# Sheet1.net
KiCad netlist of a schematic drawn in Altium Designer
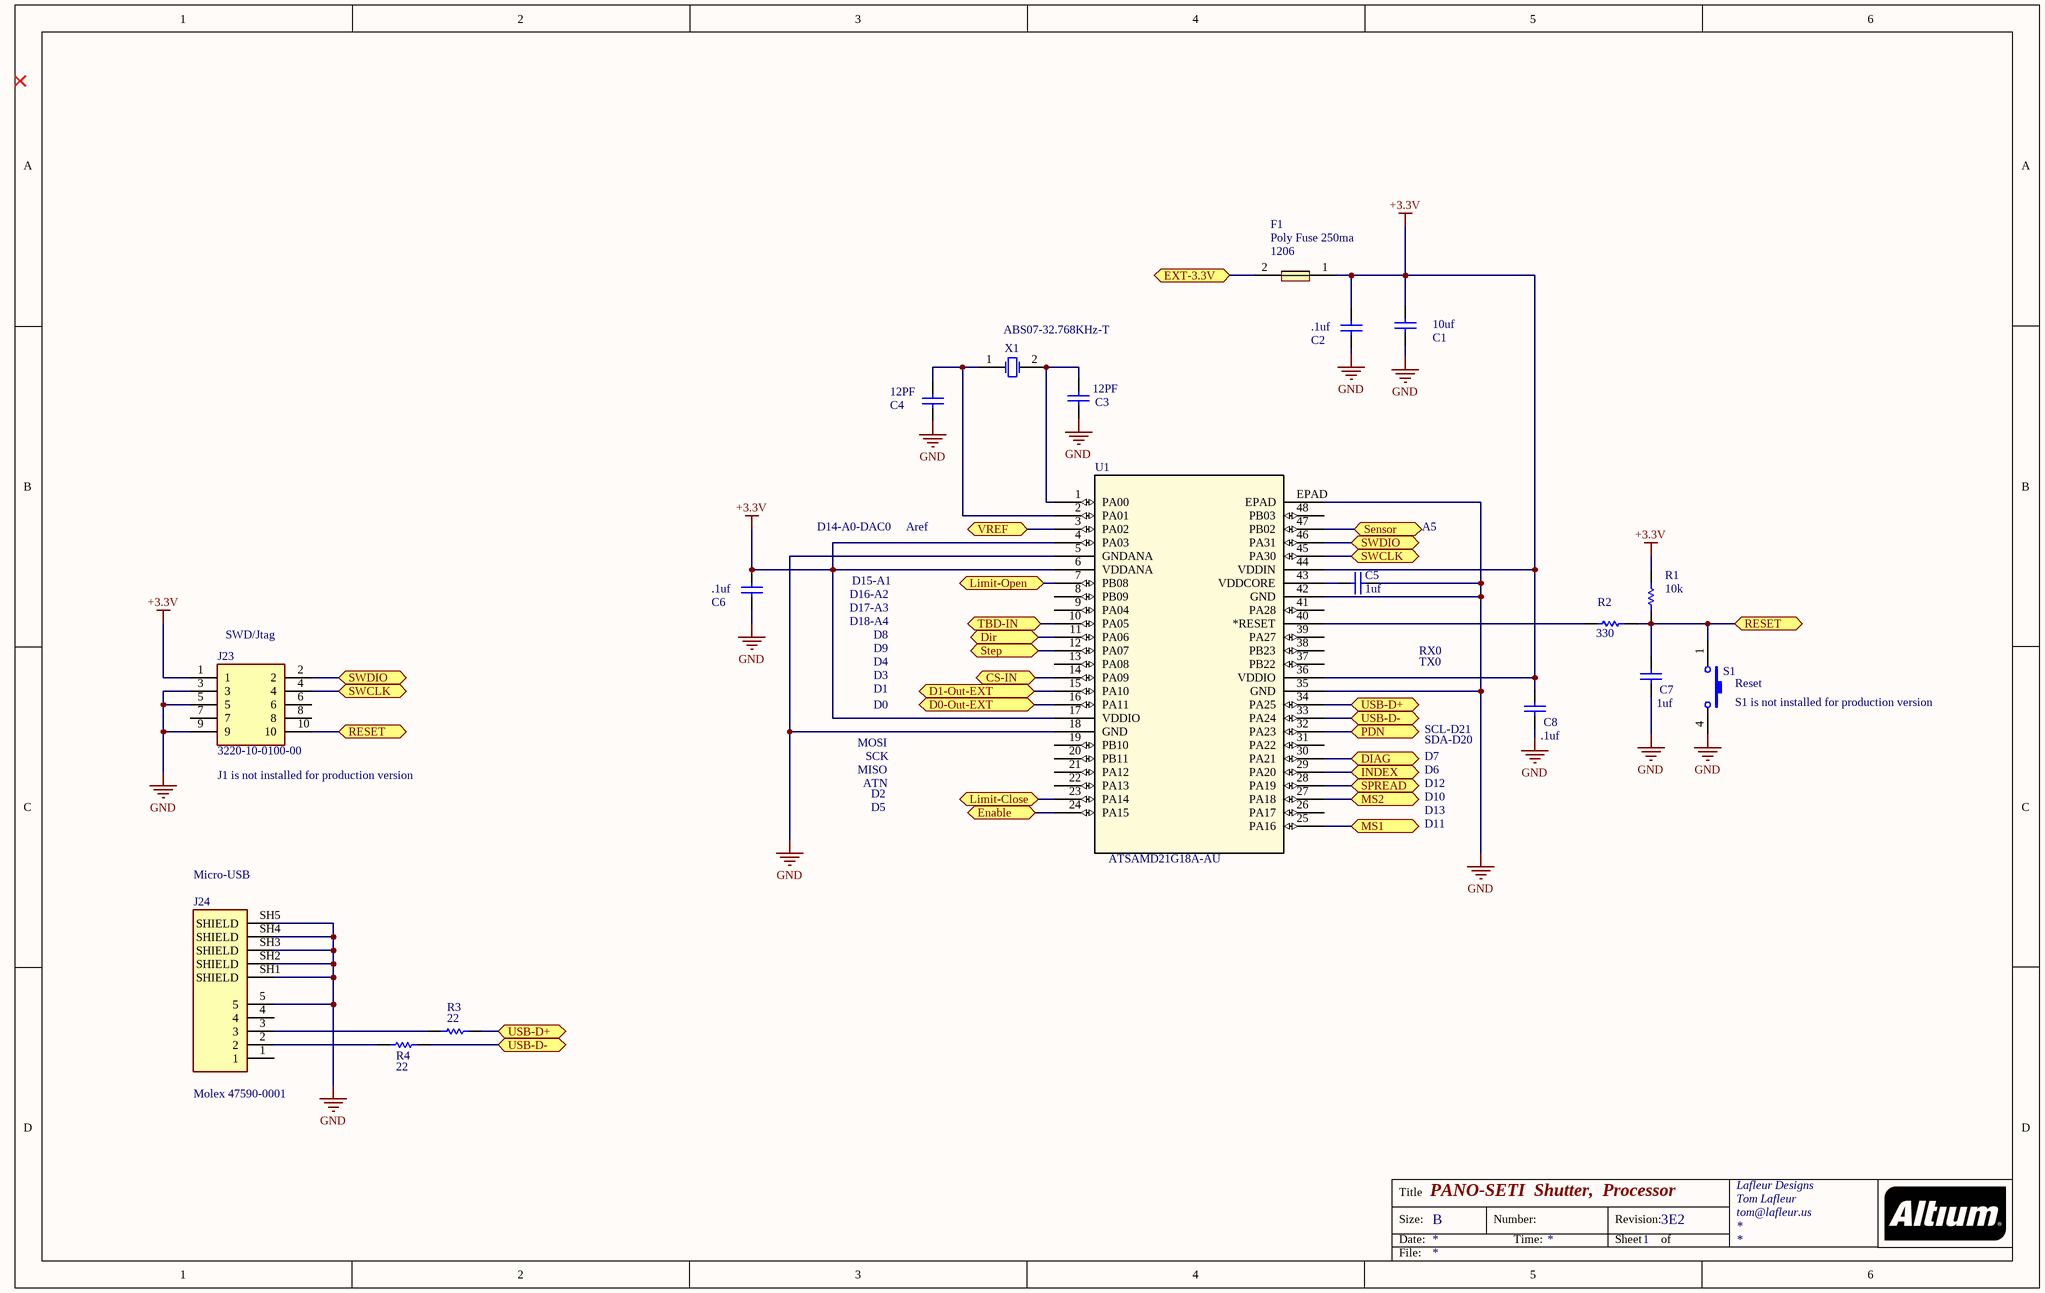
[diagram p0: Sheet1.SchDoc]

(export (version "E")
  (design (tool "Eeschema 10.0.6"))
  (components
    (comp (ref "C1")
      (value "10uf")
      (footprint "6-0805")
      (description "Capacitor")
      (libsource (lib "Winmor-Demo-R2") (part "CAP_2"))
    )
    (comp (ref "C2")
      (value ".1uf")
      (footprint "6-0805")
      (description "Capacitor")
      (libsource (lib "Winmor-Demo-R2") (part "CAP_2"))
    )
    (comp (ref "C3")
      (value "12PF")
      (footprint "6-0805")
      (description "Capacitor")
      (libsource (lib "Winmor-Demo-R2") (part "CAP_2"))
    )
    (comp (ref "C4")
      (value "12PF")
      (footprint "6-0805")
      (description "Capacitor")
      (libsource (lib "Winmor-Demo-R2") (part "CAP_2"))
    )
    (comp (ref "C5")
      (value "1uf")
      (footprint "6-0805")
      (description "Capacitor")
      (libsource (lib "Winmor-Demo-R2") (part "CAP_2"))
    )
    (comp (ref "C6")
      (value ".1uf")
      (footprint "6-0805")
      (description "Capacitor")
      (libsource (lib "Winmor-Demo-R2") (part "CAP_2"))
    )
    (comp (ref "C7")
      (value "1uf")
      (footprint "6-0805")
      (description "Capacitor")
      (libsource (lib "Winmor-Demo-R2") (part "CAP_2"))
    )
    (comp (ref "C8")
      (value ".1uf")
      (footprint "6-0805")
      (description "Capacitor")
      (libsource (lib "Winmor-Demo-R2") (part "CAP_2"))
    )
    (comp (ref "F1")
      (value "Poly Fuse 250ma")
      (footprint "8-1206")
      (description "Poly Fuse")
      (libsource (lib "N2K Project") (part "Poly Fuse"))
    )
    (comp (ref "J23")
      (value "3220-10-0100-00")
      (footprint "SHDR10W41P127_2X5_1265X510X565P")
      (description "Connector")
      (libsource (lib "*") (part "3220-10-0100-00"))
    )
    (comp (ref "J24")
      (value "Molex 47590-0001")
      (footprint "Molex 47590-0001")
      (description "USB - micro AB Receptacle Connector 5 Position Surface Mount, Right Angle; Through Hole")
      (fields (field (name "MF") "Molex") (field (name "MP") "47590-0001"))
      (libsource (lib "SnapEDAsch") (part "47590-0001"))
    )
    (comp (ref "R1")
      (value "10k")
      (footprint "6-0805")
      (description "Precision Thick Film Chip Resistor, 10 Ohm to 2.2M Ohm Range, 1% Tolerance, 1206 Size, 0.125 W")
      (fields (field (name "PUBLISHER") "Altium Limited"))
      (libsource (lib "N2K Project") (part "ERJ8EN"))
    )
    (comp (ref "R2")
      (value "330")
      (footprint "6-0805")
      (description "Precision Thick Film Chip Resistor, 10 Ohm to 2.2M Ohm Range, 1% Tolerance, 1206 Size, 0.125 W")
      (fields (field (name "PUBLISHER") "Altium Limited"))
      (libsource (lib "N2K Project") (part "ERJ8EN"))
    )
    (comp (ref "R3")
      (value "22")
      (footprint "6-0805")
      (description "Precision Thick Film Chip Resistor, 10 Ohm to 2.2M Ohm Range, 1% Tolerance, 1206 Size, 0.125 W")
      (fields (field (name "PUBLISHER") "Altium Limited"))
      (libsource (lib "N2K Project") (part "ERJ8EN"))
    )
    (comp (ref "R4")
      (value "22")
      (footprint "6-0805")
      (description "Precision Thick Film Chip Resistor, 10 Ohm to 2.2M Ohm Range, 1% Tolerance, 1206 Size, 0.125 W")
      (fields (field (name "PUBLISHER") "Altium Limited"))
      (libsource (lib "N2K Project") (part "ERJ8EN"))
    )
    (comp (ref "S1")
      (value "Reset")
      (footprint "SamacSys:KMR_2")
      (description "Switch")
      (fields (field (name "PUBLISHER") "Altium Limited"))
      (libsource (lib "Miscellaneous Devices") (part "SW-PB"))
    )
    (comp (ref "U1")
      (value "ATSAMD21G18A-AU")
      (footprint "TQFP48_7x7MC")
      (description "No Description Available")
      (fields (field (name "COPYRIGHT") "Copyright (C) 2018 Accelerated Designs. All rights reserved"))
      (libsource (lib "ATSAMD21G18") (part "ATSAMD21G18A-AU"))
    )
    (comp (ref "X1")
      (value "ABS07-32.768KHz-T")
      (footprint "ABRA-ABS07-2_V")
      (description "Crystal, 32.768 kHz, 12.5 pF, -40 to 85 degC, SMD Low Profile 3.2 x 1.5 x 0.9 mm, Tape and Reel")
      (fields (field (name "MANUFACTURER") "Abracon"))
      (libsource (lib "Altium Content Vault") (part "ABRA-ABS07-2"))
    )
  )
  (nets
    (net (code "1") (name "+3.3V") (class "Default")
      (node (ref "C1") (pin "1") (pinfunction "1_1") (pintype "passive"))
      (node (ref "C2") (pin "1") (pinfunction "1_1") (pintype "passive"))
      (node (ref "C6") (pin "1") (pinfunction "1_1") (pintype "passive"))
      (node (ref "C8") (pin "1") (pinfunction "1_1") (pintype "passive"))
      (node (ref "F1") (pin "1") (pinfunction "1_1") (pintype "passive"))
      (node (ref "J23") (pin "1") (pinfunction "1_1") (pintype "passive"))
      (node (ref "R1") (pin "1") (pinfunction "1_1") (pintype "passive"))
      (node (ref "U1") (pin "17") (pinfunction "VDDIO_17") (pintype "power_in"))
      (node (ref "U1") (pin "36") (pinfunction "VDDIO_36") (pintype "power_in"))
      (node (ref "U1") (pin "4") (pinfunction "PA03_4") (pintype "bidirectional"))
      (node (ref "U1") (pin "44") (pinfunction "VDDIN_44") (pintype "power_in"))
      (node (ref "U1") (pin "6") (pinfunction "VDDANA_6") (pintype "power_in"))
    )
    (net (code "2") (name "/CS-IN") (class "Default")
      (node (ref "U1") (pin "14") (pinfunction "PA09_14") (pintype "bidirectional"))
    )
    (net (code "3") (name "/D0-Out-EXT") (class "Default")
      (node (ref "U1") (pin "16") (pinfunction "PA11_16") (pintype "bidirectional"))
    )
    (net (code "4") (name "/D1-Out-EXT") (class "Default")
      (node (ref "U1") (pin "15") (pinfunction "PA10_15") (pintype "bidirectional"))
    )
    (net (code "5") (name "/DIAG") (class "Default")
      (node (ref "U1") (pin "30") (pinfunction "PA21_30") (pintype "bidirectional"))
    )
    (net (code "6") (name "/Dir") (class "Default")
      (node (ref "U1") (pin "11") (pinfunction "PA06_11") (pintype "bidirectional"))
    )
    (net (code "7") (name "/EXT-3.3V") (class "Default")
      (node (ref "F1") (pin "2") (pinfunction "2_2") (pintype "passive"))
    )
    (net (code "8") (name "/Enable") (class "Default")
      (node (ref "U1") (pin "24") (pinfunction "PA15_24") (pintype "bidirectional"))
    )
    (net (code "9") (name "/INDEX") (class "Default")
      (node (ref "U1") (pin "29") (pinfunction "PA20_29") (pintype "bidirectional"))
    )
    (net (code "10") (name "/Limit-Close") (class "Default")
      (node (ref "U1") (pin "23") (pinfunction "PA14_23") (pintype "bidirectional"))
    )
    (net (code "11") (name "/Limit-Open") (class "Default")
      (node (ref "U1") (pin "7") (pinfunction "PB08_7") (pintype "bidirectional"))
    )
    (net (code "12") (name "/MS1") (class "Default")
      (node (ref "U1") (pin "25") (pinfunction "PA16_25") (pintype "bidirectional"))
    )
    (net (code "13") (name "/MS2") (class "Default")
      (node (ref "U1") (pin "27") (pinfunction "PA18_27") (pintype "bidirectional"))
    )
    (net (code "14") (name "/PDN") (class "Default")
      (node (ref "U1") (pin "32") (pinfunction "PA23_32") (pintype "bidirectional"))
    )
    (net (code "15") (name "/RESET") (class "Default")
      (node (ref "C7") (pin "1") (pinfunction "1_1") (pintype "passive"))
      (node (ref "J23") (pin "10") (pinfunction "10_10") (pintype "passive"))
      (node (ref "R1") (pin "2") (pinfunction "2_2") (pintype "passive"))
      (node (ref "R2") (pin "2") (pinfunction "2_2") (pintype "passive"))
      (node (ref "S1") (pin "1") (pinfunction "1_1") (pintype "passive"))
    )
    (net (code "16") (name "/SPREAD") (class "Default")
      (node (ref "U1") (pin "28") (pinfunction "PA19_28") (pintype "bidirectional"))
    )
    (net (code "17") (name "/SWCLK") (class "Default")
      (node (ref "J23") (pin "4") (pinfunction "4_4") (pintype "passive"))
      (node (ref "U1") (pin "45") (pinfunction "PA30_45") (pintype "bidirectional"))
    )
    (net (code "18") (name "/SWDIO") (class "Default")
      (node (ref "J23") (pin "2") (pinfunction "2_2") (pintype "passive"))
      (node (ref "U1") (pin "46") (pinfunction "PA31_46") (pintype "bidirectional"))
    )
    (net (code "19") (name "/Sensor") (class "Default")
      (node (ref "U1") (pin "47") (pinfunction "PB02_47") (pintype "bidirectional"))
    )
    (net (code "20") (name "/Step") (class "Default")
      (node (ref "U1") (pin "12") (pinfunction "PA07_12") (pintype "bidirectional"))
    )
    (net (code "21") (name "/TBD-IN") (class "Default")
      (node (ref "U1") (pin "10") (pinfunction "PA05_10") (pintype "bidirectional"))
    )
    (net (code "22") (name "/USB-D+") (class "Default")
      (node (ref "R3") (pin "2") (pinfunction "2_2") (pintype "passive"))
      (node (ref "U1") (pin "34") (pinfunction "PA25_34") (pintype "bidirectional"))
    )
    (net (code "23") (name "/USB-D-") (class "Default")
      (node (ref "R4") (pin "2") (pinfunction "2_2") (pintype "passive"))
      (node (ref "U1") (pin "33") (pinfunction "PA24_33") (pintype "bidirectional"))
    )
    (net (code "24") (name "/VREF") (class "Default")
      (node (ref "U1") (pin "3") (pinfunction "PA02_3") (pintype "bidirectional"))
    )
    (net (code "25") (name "GND") (class "Default")
      (node (ref "C1") (pin "2") (pinfunction "2_2") (pintype "passive"))
      (node (ref "C2") (pin "2") (pinfunction "2_2") (pintype "passive"))
      (node (ref "C3") (pin "2") (pinfunction "2_2") (pintype "passive"))
      (node (ref "C4") (pin "2") (pinfunction "2_2") (pintype "passive"))
      (node (ref "C5") (pin "2") (pinfunction "2_2") (pintype "passive"))
      (node (ref "C6") (pin "2") (pinfunction "2_2") (pintype "passive"))
      (node (ref "C7") (pin "2") (pinfunction "2_2") (pintype "passive"))
      (node (ref "C8") (pin "2") (pinfunction "2_2") (pintype "passive"))
      (node (ref "J23") (pin "3") (pinfunction "3_3") (pintype "passive"))
      (node (ref "J23") (pin "5") (pinfunction "5_5") (pintype "passive"))
      (node (ref "J23") (pin "9") (pinfunction "9_9") (pintype "passive"))
      (node (ref "J24") (pin "5") (pinfunction "5_5") (pintype "passive"))
      (node (ref "J24") (pin "SH1") (pinfunction "SHIELD_SH1") (pintype "passive"))
      (node (ref "J24") (pin "SH2") (pinfunction "SHIELD_SH2") (pintype "passive"))
      (node (ref "J24") (pin "SH3") (pinfunction "SHIELD_SH3") (pintype "passive"))
      (node (ref "J24") (pin "SH4") (pinfunction "SHIELD_SH4") (pintype "passive"))
      (node (ref "J24") (pin "SH5") (pinfunction "SHIELD_SH5") (pintype "passive"))
      (node (ref "S1") (pin "4") (pinfunction "4_4") (pintype "passive"))
      (node (ref "U1") (pin "18") (pinfunction "GND_18") (pintype "passive"))
      (node (ref "U1") (pin "35") (pinfunction "GND_35") (pintype "passive"))
      (node (ref "U1") (pin "42") (pinfunction "GND_42") (pintype "passive"))
      (node (ref "U1") (pin "5") (pinfunction "GNDANA_5") (pintype "passive"))
      (node (ref "U1") (pin "EPAD") (pinfunction "EPAD_EPAD") (pintype "passive"))
    )
    (net (code "26") (name "Net-(J24-Pad2)") (class "Default")
      (node (ref "J24") (pin "2") (pinfunction "2_2") (pintype "passive"))
      (node (ref "R4") (pin "1") (pinfunction "1_1") (pintype "passive"))
    )
    (net (code "27") (name "Net-(J24-Pad3)") (class "Default")
      (node (ref "J24") (pin "3") (pinfunction "3_3") (pintype "passive"))
      (node (ref "R3") (pin "1") (pinfunction "1_1") (pintype "passive"))
    )
    (net (code "28") (name "Net-(U1-*RESET)") (class "Default")
      (node (ref "R2") (pin "1") (pinfunction "1_1") (pintype "passive"))
      (node (ref "U1") (pin "40") (pinfunction "*RESET_40") (pintype "passive"))
    )
    (net (code "29") (name "Net-(U1-PA00)") (class "Default")
      (node (ref "C3") (pin "1") (pinfunction "1_1") (pintype "passive"))
      (node (ref "U1") (pin "1") (pinfunction "PA00_1") (pintype "bidirectional"))
      (node (ref "X1") (pin "2") (pinfunction "X2_2") (pintype "passive"))
    )
    (net (code "30") (name "Net-(U1-PA01)") (class "Default")
      (node (ref "C4") (pin "1") (pinfunction "1_1") (pintype "passive"))
      (node (ref "U1") (pin "2") (pinfunction "PA01_2") (pintype "bidirectional"))
      (node (ref "X1") (pin "1") (pinfunction "X1_1") (pintype "passive"))
    )
    (net (code "31") (name "Net-(U1-VDDCORE)") (class "Default")
      (node (ref "C5") (pin "1") (pinfunction "1_1") (pintype "passive"))
      (node (ref "U1") (pin "43") (pinfunction "VDDCORE_43") (pintype "power_in"))
    )
    (net (code "32") (name "unconnected-(J23-Pad6)") (class "Default")
      (node (ref "J23") (pin "6") (pinfunction "6_6") (pintype "passive"))
    )
    (net (code "33") (name "unconnected-(J23-Pad7)") (class "Default")
      (node (ref "J23") (pin "7") (pinfunction "7_7") (pintype "passive"))
    )
    (net (code "34") (name "unconnected-(J23-Pad8)") (class "Default")
      (node (ref "J23") (pin "8") (pinfunction "8_8") (pintype "passive"))
    )
    (net (code "35") (name "unconnected-(J24-Pad1)") (class "Default")
      (node (ref "J24") (pin "1") (pinfunction "1_1") (pintype "passive"))
    )
    (net (code "36") (name "unconnected-(J24-Pad4)") (class "Default")
      (node (ref "J24") (pin "4") (pinfunction "4_4") (pintype "passive"))
    )
    (net (code "37") (name "unconnected-(U1-PA04-Pad9)") (class "Default")
      (node (ref "U1") (pin "9") (pinfunction "PA04_9") (pintype "bidirectional"))
    )
    (net (code "38") (name "unconnected-(U1-PA08-Pad13)") (class "Default")
      (node (ref "U1") (pin "13") (pinfunction "PA08_13") (pintype "bidirectional"))
    )
    (net (code "39") (name "unconnected-(U1-PA12-Pad21)") (class "Default")
      (node (ref "U1") (pin "21") (pinfunction "PA12_21") (pintype "bidirectional"))
    )
    (net (code "40") (name "unconnected-(U1-PA13-Pad22)") (class "Default")
      (node (ref "U1") (pin "22") (pinfunction "PA13_22") (pintype "bidirectional"))
    )
    (net (code "41") (name "unconnected-(U1-PA17-Pad26)") (class "Default")
      (node (ref "U1") (pin "26") (pinfunction "PA17_26") (pintype "bidirectional"))
    )
    (net (code "42") (name "unconnected-(U1-PA22-Pad31)") (class "Default")
      (node (ref "U1") (pin "31") (pinfunction "PA22_31") (pintype "bidirectional"))
    )
    (net (code "43") (name "unconnected-(U1-PA27-Pad39)") (class "Default")
      (node (ref "U1") (pin "39") (pinfunction "PA27_39") (pintype "bidirectional"))
    )
    (net (code "44") (name "unconnected-(U1-PA28-Pad41)") (class "Default")
      (node (ref "U1") (pin "41") (pinfunction "PA28_41") (pintype "bidirectional"))
    )
    (net (code "45") (name "unconnected-(U1-PB03-Pad48)") (class "Default")
      (node (ref "U1") (pin "48") (pinfunction "PB03_48") (pintype "bidirectional"))
    )
    (net (code "46") (name "unconnected-(U1-PB09-Pad8)") (class "Default")
      (node (ref "U1") (pin "8") (pinfunction "PB09_8") (pintype "bidirectional"))
    )
    (net (code "47") (name "unconnected-(U1-PB10-Pad19)") (class "Default")
      (node (ref "U1") (pin "19") (pinfunction "PB10_19") (pintype "bidirectional"))
    )
    (net (code "48") (name "unconnected-(U1-PB11-Pad20)") (class "Default")
      (node (ref "U1") (pin "20") (pinfunction "PB11_20") (pintype "bidirectional"))
    )
    (net (code "49") (name "unconnected-(U1-PB22-Pad37)") (class "Default")
      (node (ref "U1") (pin "37") (pinfunction "PB22_37") (pintype "bidirectional"))
    )
    (net (code "50") (name "unconnected-(U1-PB23-Pad38)") (class "Default")
      (node (ref "U1") (pin "38") (pinfunction "PB23_38") (pintype "bidirectional"))
    )
  )
)
